# msp432_breakout_hm10.net
KiCad netlist of a schematic drawn in EAGLE
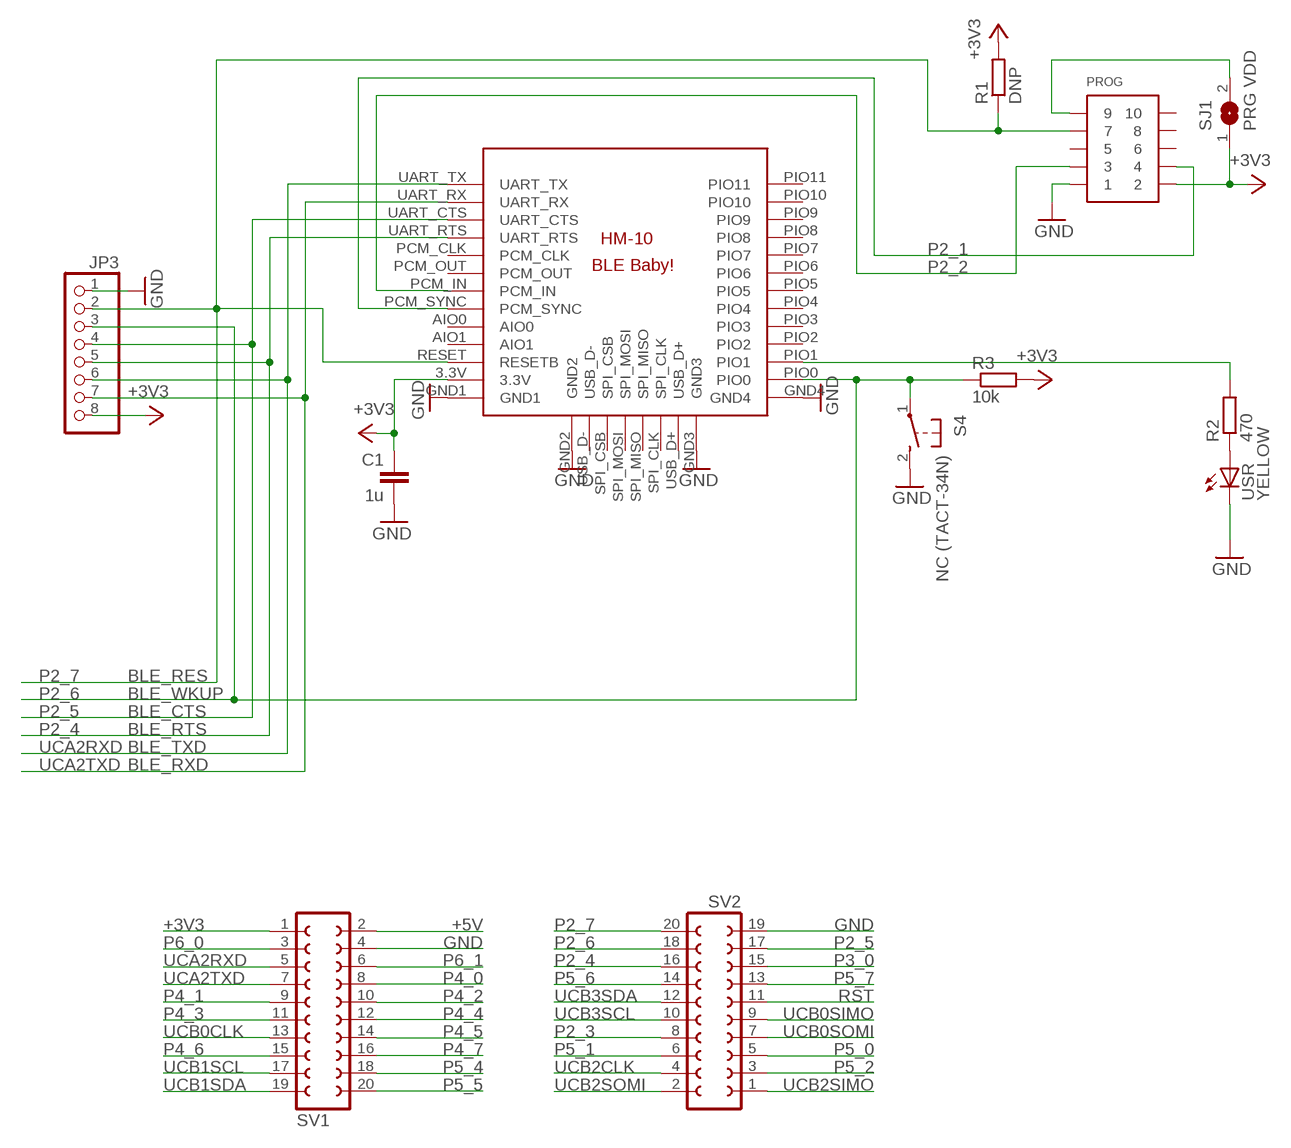
[diagram p0: schematic, sheet 1]

(export (version "E")
  (design (tool "Eeschema 10.0.6"))
  (components
    (comp (ref "C1")
      (value "1u")
      (footprint "eagle-import:C0603")
      (libsource (lib "eagle-import") (part "C-EUC0603"))
    )
    (comp (ref "JP3")
      (value "PINHD-1X8")
      (footprint "eagle-import:1X08")
      (libsource (lib "eagle-import") (part "PINHD-1X8"))
    )
    (comp (ref "PROG")
      (value "CONN_5-2-FTSH-V")
      (footprint "eagle-import:FTSH-105-DV")
      (libsource (lib "eagle-import") (part "CONN_5-2-FTSH-V"))
    )
    (comp (ref "R1")
      (value "DNP")
      (footprint "eagle-import:R0603")
      (libsource (lib "eagle-import") (part "R-EU_R0603"))
    )
    (comp (ref "R2")
      (value "470")
      (footprint "eagle-import:R0603")
      (libsource (lib "eagle-import") (part "R-EU_R0603"))
    )
    (comp (ref "R3")
      (value "10k")
      (footprint "eagle-import:R0603")
      (libsource (lib "eagle-import") (part "R-EU_R0603"))
    )
    (comp (ref "S4")
      (value "NC (TACT-34N)")
      (footprint "eagle-import:TACT-34N")
      (libsource (lib "eagle-import") (part "TACT-34N"))
    )
    (comp (ref "SJ1")
      (value "PRG VDD")
      (footprint "eagle-import:SJ")
      (libsource (lib "eagle-import") (part "SJ"))
    )
    (comp (ref "SV1")
      (value "FE10-2")
      (footprint "eagle-import:FE10-2")
      (libsource (lib "eagle-import") (part "FE10-2"))
    )
    (comp (ref "SV2")
      (value "FE10-2")
      (footprint "eagle-import:FE10-2")
      (libsource (lib "eagle-import") (part "FE10-2"))
    )
    (comp (ref "U$1")
      (value "BLE-HM-10")
      (footprint "eagle-import:BLE-HM-10")
      (libsource (lib "eagle-import") (part "BLE-HM-10"))
    )
    (comp (ref "USR")
      (value "YELLOW")
      (footprint "eagle-import:CHIPLED_0805")
      (libsource (lib "eagle-import") (part "LEDCHIPLED_0805"))
    )
  )
  (nets
    (net (code "1") (name "+3V3") (class "Default")
      (node (ref "C1") (pin "1") (pinfunction "1_1") (pintype "passive"))
      (node (ref "JP3") (pin "8") (pinfunction "8_8") (pintype "passive"))
      (node (ref "PROG") (pin "2") (pinfunction "2_2") (pintype "bidirectional"))
      (node (ref "R1") (pin "2") (pinfunction "2_2") (pintype "passive"))
      (node (ref "R3") (pin "2") (pinfunction "2_2") (pintype "passive"))
      (node (ref "SJ1") (pin "1") (pinfunction "1_1") (pintype "passive"))
      (node (ref "SV1") (pin "1") (pinfunction "1_1") (pintype "passive"))
      (node (ref "U$1") (pin "3.3V") (pinfunction "3.3V_3.3V") (pintype "bidirectional"))
    )
    (net (code "2") (name "/+5V") (class "Default")
      (node (ref "SV1") (pin "2") (pinfunction "2_2") (pintype "passive"))
    )
    (net (code "3") (name "/P2_1") (class "Default")
      (node (ref "PROG") (pin "4") (pinfunction "4_4") (pintype "bidirectional"))
      (node (ref "U$1") (pin "PCM_SYNC") (pinfunction "PCM_SYNC_PCM_SYNC") (pintype "bidirectional"))
    )
    (net (code "4") (name "/P2_2") (class "Default")
      (node (ref "PROG") (pin "3") (pinfunction "3_3") (pintype "bidirectional"))
      (node (ref "U$1") (pin "PCM_IN") (pinfunction "PCM_IN_PCM_IN") (pintype "bidirectional"))
    )
    (net (code "5") (name "/P2_3") (class "Default")
      (node (ref "SV2") (pin "8") (pinfunction "8_8") (pintype "passive"))
    )
    (net (code "6") (name "/P2_4") (class "Default")
      (node (ref "JP3") (pin "5") (pinfunction "5_5") (pintype "passive"))
      (node (ref "SV2") (pin "16") (pinfunction "16_16") (pintype "passive"))
      (node (ref "U$1") (pin "UART_RTS") (pinfunction "UART_RTS_UART_RTS") (pintype "bidirectional"))
    )
    (net (code "7") (name "/P2_5") (class "Default")
      (node (ref "JP3") (pin "4") (pinfunction "4_4") (pintype "passive"))
      (node (ref "SV2") (pin "17") (pinfunction "17_17") (pintype "passive"))
      (node (ref "U$1") (pin "UART_CTS") (pinfunction "UART_CTS_UART_CTS") (pintype "bidirectional"))
    )
    (net (code "8") (name "/P2_6") (class "Default")
      (node (ref "JP3") (pin "3") (pinfunction "3_3") (pintype "passive"))
      (node (ref "R3") (pin "1") (pinfunction "1_1") (pintype "passive"))
      (node (ref "S4") (pin "1") (pinfunction "P_1") (pintype "passive"))
      (node (ref "SV2") (pin "18") (pinfunction "18_18") (pintype "passive"))
      (node (ref "U$1") (pin "PIO0") (pinfunction "PIO0_PIO0") (pintype "bidirectional"))
    )
    (net (code "9") (name "/P2_7") (class "Default")
      (node (ref "JP3") (pin "2") (pinfunction "2_2") (pintype "passive"))
      (node (ref "PROG") (pin "7") (pinfunction "7_7") (pintype "bidirectional"))
      (node (ref "R1") (pin "1") (pinfunction "1_1") (pintype "passive"))
      (node (ref "SV2") (pin "20") (pinfunction "20_20") (pintype "passive"))
      (node (ref "U$1") (pin "RESET") (pinfunction "RESETB_RESET") (pintype "bidirectional"))
    )
    (net (code "10") (name "/P3_0") (class "Default")
      (node (ref "SV2") (pin "15") (pinfunction "15_15") (pintype "passive"))
    )
    (net (code "11") (name "/P4_0") (class "Default")
      (node (ref "SV1") (pin "8") (pinfunction "8_8") (pintype "passive"))
    )
    (net (code "12") (name "/P4_1") (class "Default")
      (node (ref "SV1") (pin "9") (pinfunction "9_9") (pintype "passive"))
    )
    (net (code "13") (name "/P4_2") (class "Default")
      (node (ref "SV1") (pin "10") (pinfunction "10_10") (pintype "passive"))
    )
    (net (code "14") (name "/P4_3") (class "Default")
      (node (ref "SV1") (pin "11") (pinfunction "11_11") (pintype "passive"))
    )
    (net (code "15") (name "/P4_4") (class "Default")
      (node (ref "SV1") (pin "12") (pinfunction "12_12") (pintype "passive"))
    )
    (net (code "16") (name "/P4_5") (class "Default")
      (node (ref "SV1") (pin "14") (pinfunction "14_14") (pintype "passive"))
    )
    (net (code "17") (name "/P4_6") (class "Default")
      (node (ref "SV1") (pin "15") (pinfunction "15_15") (pintype "passive"))
    )
    (net (code "18") (name "/P4_7") (class "Default")
      (node (ref "SV1") (pin "16") (pinfunction "16_16") (pintype "passive"))
    )
    (net (code "19") (name "/P5_0") (class "Default")
      (node (ref "SV2") (pin "5") (pinfunction "5_5") (pintype "passive"))
    )
    (net (code "20") (name "/P5_1") (class "Default")
      (node (ref "SV2") (pin "6") (pinfunction "6_6") (pintype "passive"))
    )
    (net (code "21") (name "/P5_2") (class "Default")
      (node (ref "SV2") (pin "3") (pinfunction "3_3") (pintype "passive"))
    )
    (net (code "22") (name "/P5_4") (class "Default")
      (node (ref "SV1") (pin "18") (pinfunction "18_18") (pintype "passive"))
    )
    (net (code "23") (name "/P5_5") (class "Default")
      (node (ref "SV1") (pin "20") (pinfunction "20_20") (pintype "passive"))
    )
    (net (code "24") (name "/P5_6") (class "Default")
      (node (ref "SV2") (pin "14") (pinfunction "14_14") (pintype "passive"))
    )
    (net (code "25") (name "/P5_7") (class "Default")
      (node (ref "SV2") (pin "13") (pinfunction "13_13") (pintype "passive"))
    )
    (net (code "26") (name "/P6_0") (class "Default")
      (node (ref "SV1") (pin "3") (pinfunction "3_3") (pintype "passive"))
    )
    (net (code "27") (name "/P6_1") (class "Default")
      (node (ref "SV1") (pin "6") (pinfunction "6_6") (pintype "passive"))
    )
    (net (code "28") (name "/RST") (class "Default")
      (node (ref "SV2") (pin "11") (pinfunction "11_11") (pintype "passive"))
    )
    (net (code "29") (name "/UCA2RXD") (class "Default")
      (node (ref "JP3") (pin "6") (pinfunction "6_6") (pintype "passive"))
      (node (ref "SV1") (pin "5") (pinfunction "5_5") (pintype "passive"))
      (node (ref "U$1") (pin "UART_TX") (pinfunction "UART_TX_UART_TX") (pintype "bidirectional"))
    )
    (net (code "30") (name "/UCA2TXD") (class "Default")
      (node (ref "JP3") (pin "7") (pinfunction "7_7") (pintype "passive"))
      (node (ref "SV1") (pin "7") (pinfunction "7_7") (pintype "passive"))
      (node (ref "U$1") (pin "UART_RX") (pinfunction "UART_RX_UART_RX") (pintype "bidirectional"))
    )
    (net (code "31") (name "/UCB0CLK") (class "Default")
      (node (ref "SV1") (pin "13") (pinfunction "13_13") (pintype "passive"))
    )
    (net (code "32") (name "/UCB0SIMO") (class "Default")
      (node (ref "SV2") (pin "9") (pinfunction "9_9") (pintype "passive"))
    )
    (net (code "33") (name "/UCB0SOMI") (class "Default")
      (node (ref "SV2") (pin "7") (pinfunction "7_7") (pintype "passive"))
    )
    (net (code "34") (name "/UCB1SCL") (class "Default")
      (node (ref "SV1") (pin "17") (pinfunction "17_17") (pintype "passive"))
    )
    (net (code "35") (name "/UCB1SDA") (class "Default")
      (node (ref "SV1") (pin "19") (pinfunction "19_19") (pintype "passive"))
    )
    (net (code "36") (name "/UCB2CLK") (class "Default")
      (node (ref "SV2") (pin "4") (pinfunction "4_4") (pintype "passive"))
    )
    (net (code "37") (name "/UCB2SIMO") (class "Default")
      (node (ref "SV2") (pin "1") (pinfunction "1_1") (pintype "passive"))
    )
    (net (code "38") (name "/UCB2SOMI") (class "Default")
      (node (ref "SV2") (pin "2") (pinfunction "2_2") (pintype "passive"))
    )
    (net (code "39") (name "/UCB3SCL") (class "Default")
      (node (ref "SV2") (pin "10") (pinfunction "10_10") (pintype "passive"))
    )
    (net (code "40") (name "/UCB3SDA") (class "Default")
      (node (ref "SV2") (pin "12") (pinfunction "12_12") (pintype "passive"))
    )
    (net (code "41") (name "GND") (class "Default")
      (node (ref "C1") (pin "2") (pinfunction "2_2") (pintype "passive"))
      (node (ref "JP3") (pin "1") (pinfunction "1_1") (pintype "passive"))
      (node (ref "PROG") (pin "1") (pinfunction "1_1") (pintype "bidirectional"))
      (node (ref "S4") (pin "2") (pinfunction "S_2") (pintype "passive"))
      (node (ref "SV1") (pin "4") (pinfunction "4_4") (pintype "passive"))
      (node (ref "SV2") (pin "19") (pinfunction "19_19") (pintype "passive"))
      (node (ref "U$1") (pin "GND1") (pinfunction "GND1_GND1") (pintype "bidirectional"))
      (node (ref "U$1") (pin "GND2") (pinfunction "GND2_GND2") (pintype "bidirectional"))
      (node (ref "U$1") (pin "GND3") (pinfunction "GND3_GND3") (pintype "bidirectional"))
      (node (ref "U$1") (pin "GND4") (pinfunction "GND4_GND4") (pintype "bidirectional"))
      (node (ref "USR") (pin "C") (pinfunction "C_C") (pintype "passive"))
    )
    (net (code "42") (name "Net-(PROG-Pad9)") (class "Default")
      (node (ref "PROG") (pin "9") (pinfunction "9_9") (pintype "bidirectional"))
      (node (ref "SJ1") (pin "2") (pinfunction "2_2") (pintype "passive"))
    )
    (net (code "43") (name "Net-(R2-Pad1)") (class "Default")
      (node (ref "R2") (pin "1") (pinfunction "1_1") (pintype "passive"))
      (node (ref "USR") (pin "A") (pinfunction "A_A") (pintype "passive"))
    )
    (net (code "44") (name "Net-(R2-Pad2)") (class "Default")
      (node (ref "R2") (pin "2") (pinfunction "2_2") (pintype "passive"))
      (node (ref "U$1") (pin "PIO1") (pinfunction "PIO1_PIO1") (pintype "bidirectional"))
    )
    (net (code "45") (name "unconnected-(PROG-Pad5)") (class "Default")
      (node (ref "PROG") (pin "5") (pinfunction "5_5") (pintype "bidirectional"))
    )
    (net (code "46") (name "unconnected-(PROG-Pad6)") (class "Default")
      (node (ref "PROG") (pin "6") (pinfunction "6_6") (pintype "bidirectional"))
    )
    (net (code "47") (name "unconnected-(PROG-Pad8)") (class "Default")
      (node (ref "PROG") (pin "8") (pinfunction "8_8") (pintype "bidirectional"))
    )
    (net (code "48") (name "unconnected-(PROG-Pad10)") (class "Default")
      (node (ref "PROG") (pin "10") (pinfunction "10_10") (pintype "bidirectional"))
    )
    (net (code "49") (name "unconnected-(U$1-PadAIO0)") (class "Default")
      (node (ref "U$1") (pin "AIO0") (pinfunction "AIO0_AIO0") (pintype "bidirectional"))
    )
    (net (code "50") (name "unconnected-(U$1-PadAIO1)") (class "Default")
      (node (ref "U$1") (pin "AIO1") (pinfunction "AIO1_AIO1") (pintype "bidirectional"))
    )
    (net (code "51") (name "unconnected-(U$1-PadPCM_CLK)") (class "Default")
      (node (ref "U$1") (pin "PCM_CLK") (pinfunction "PCM_CLK_PCM_CLK") (pintype "bidirectional"))
    )
    (net (code "52") (name "unconnected-(U$1-PadPCM_OUT)") (class "Default")
      (node (ref "U$1") (pin "PCM_OUT") (pinfunction "PCM_OUT_PCM_OUT") (pintype "bidirectional"))
    )
    (net (code "53") (name "unconnected-(U$1-PadPIO2)") (class "Default")
      (node (ref "U$1") (pin "PIO2") (pinfunction "PIO2_PIO2") (pintype "bidirectional"))
    )
    (net (code "54") (name "unconnected-(U$1-PadPIO3)") (class "Default")
      (node (ref "U$1") (pin "PIO3") (pinfunction "PIO3_PIO3") (pintype "bidirectional"))
    )
    (net (code "55") (name "unconnected-(U$1-PadPIO4)") (class "Default")
      (node (ref "U$1") (pin "PIO4") (pinfunction "PIO4_PIO4") (pintype "bidirectional"))
    )
    (net (code "56") (name "unconnected-(U$1-PadPIO5)") (class "Default")
      (node (ref "U$1") (pin "PIO5") (pinfunction "PIO5_PIO5") (pintype "bidirectional"))
    )
    (net (code "57") (name "unconnected-(U$1-PadPIO6)") (class "Default")
      (node (ref "U$1") (pin "PIO6") (pinfunction "PIO6_PIO6") (pintype "bidirectional"))
    )
    (net (code "58") (name "unconnected-(U$1-PadPIO7)") (class "Default")
      (node (ref "U$1") (pin "PIO7") (pinfunction "PIO7_PIO7") (pintype "bidirectional"))
    )
    (net (code "59") (name "unconnected-(U$1-PadPIO8)") (class "Default")
      (node (ref "U$1") (pin "PIO8") (pinfunction "PIO8_PIO8") (pintype "bidirectional"))
    )
    (net (code "60") (name "unconnected-(U$1-PadPIO9)") (class "Default")
      (node (ref "U$1") (pin "PIO9") (pinfunction "PIO9_PIO9") (pintype "bidirectional"))
    )
    (net (code "61") (name "unconnected-(U$1-PadPIO10)") (class "Default")
      (node (ref "U$1") (pin "PIO10") (pinfunction "PIO10_PIO10") (pintype "bidirectional"))
    )
    (net (code "62") (name "unconnected-(U$1-PadPIO11)") (class "Default")
      (node (ref "U$1") (pin "PIO11") (pinfunction "PIO11_PIO11") (pintype "bidirectional"))
    )
    (net (code "63") (name "unconnected-(U$1-PadSPI_CLK)") (class "Default")
      (node (ref "U$1") (pin "SPI_CLK") (pinfunction "SPI_CLK_SPI_CLK") (pintype "bidirectional"))
    )
    (net (code "64") (name "unconnected-(U$1-PadSPI_CSB)") (class "Default")
      (node (ref "U$1") (pin "SPI_CSB") (pinfunction "SPI_CSB_SPI_CSB") (pintype "bidirectional"))
    )
    (net (code "65") (name "unconnected-(U$1-PadSPI_MISO)") (class "Default")
      (node (ref "U$1") (pin "SPI_MISO") (pinfunction "SPI_MISO_SPI_MISO") (pintype "bidirectional"))
    )
    (net (code "66") (name "unconnected-(U$1-PadSPI_MOSI)") (class "Default")
      (node (ref "U$1") (pin "SPI_MOSI") (pinfunction "SPI_MOSI_SPI_MOSI") (pintype "bidirectional"))
    )
    (net (code "67") (name "unconnected-(U$1-PadUSB_D+)") (class "Default")
      (node (ref "U$1") (pin "USB_D+") (pinfunction "USB_D+_USB_D+") (pintype "bidirectional"))
    )
    (net (code "68") (name "unconnected-(U$1-PadUSB_D-)") (class "Default")
      (node (ref "U$1") (pin "USB_D-") (pinfunction "USB_D-_USB_D-") (pintype "bidirectional"))
    )
  )
)
